# BUZZER.net
KiCad netlist of a schematic drawn in Altium Designer
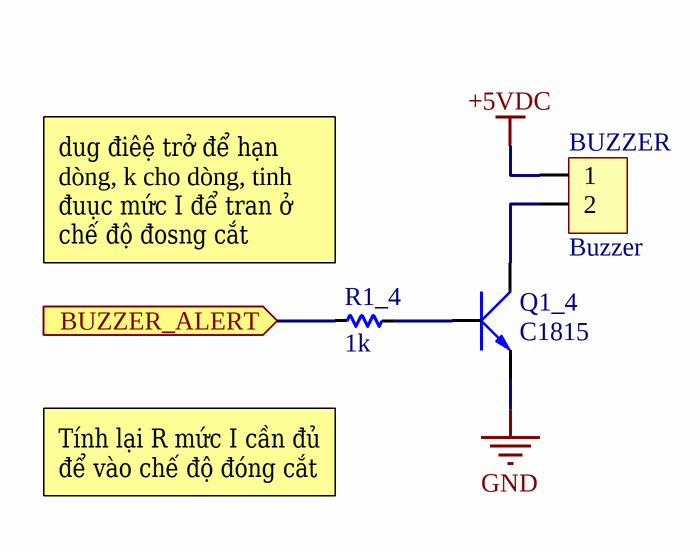
[diagram p0: BUZZER.SchDoc]

(export (version "E")
  (design (tool "Eeschema 10.0.6"))
  (components
    (comp (ref "BUZZER")
      (value "Buzzer")
      (footprint "Header2")
      (description "Header IDC, 2 x 1 Pin Vertical 2.54mm Pitch (Non-Boxed, Male)")
      (fields
        (field (name "MANUFACTURER") "Würth Elektronik eiSos GmbH")
        (field (name "PARTNO") "613002143121")
        (field (name "CREATED BY") "Karrer Zheng")
      )
      (libsource (lib "Altium Library") (part "Header2"))
    )
    (comp (ref "Q1_4")
      (value "C1815")
      (footprint "SOT23-321")
      (description "NPN 600mW, ECB")
      (libsource (lib "Altium Library") (part "2SC1815"))
    )
    (comp (ref "R1_4")
      (value "1k")
      (footprint "RES-SMD-0805")
      (description "Resistor")
      (fields
        (field (name "MANUFACTURER") "Generic Components")
        (field (name "PUBLISHER") "Altium Hobart Technology Centre")
      )
      (libsource (lib "Altium Library") (part "Res-SMD"))
    )
  )
  (nets
    (net (code "1") (name "+5VDC") (class "Default")
      (node (ref "BUZZER") (pin "1") (pinfunction "1_1") (pintype "passive"))
    )
    (net (code "2") (name "/BUZZER_ALERT") (class "Default")
      (node (ref "R1_4") (pin "2") (pinfunction "2_2") (pintype "passive"))
    )
    (net (code "3") (name "GND") (class "Default")
      (node (ref "Q1_4") (pin "1") (pinfunction "E_1") (pintype "passive"))
    )
    (net (code "4") (name "Net-(Q1_4-B)") (class "Default")
      (node (ref "Q1_4") (pin "3") (pinfunction "B_3") (pintype "passive"))
      (node (ref "R1_4") (pin "1") (pinfunction "1_1") (pintype "passive"))
    )
    (net (code "5") (name "Net-(Q1_4-C)") (class "Default")
      (node (ref "BUZZER") (pin "2") (pinfunction "2_2") (pintype "passive"))
      (node (ref "Q1_4") (pin "2") (pinfunction "C_2") (pintype "passive"))
    )
  )
)
